# max31855_sensorion_board.net
KiCad netlist of a schematic drawn in Altium Designer
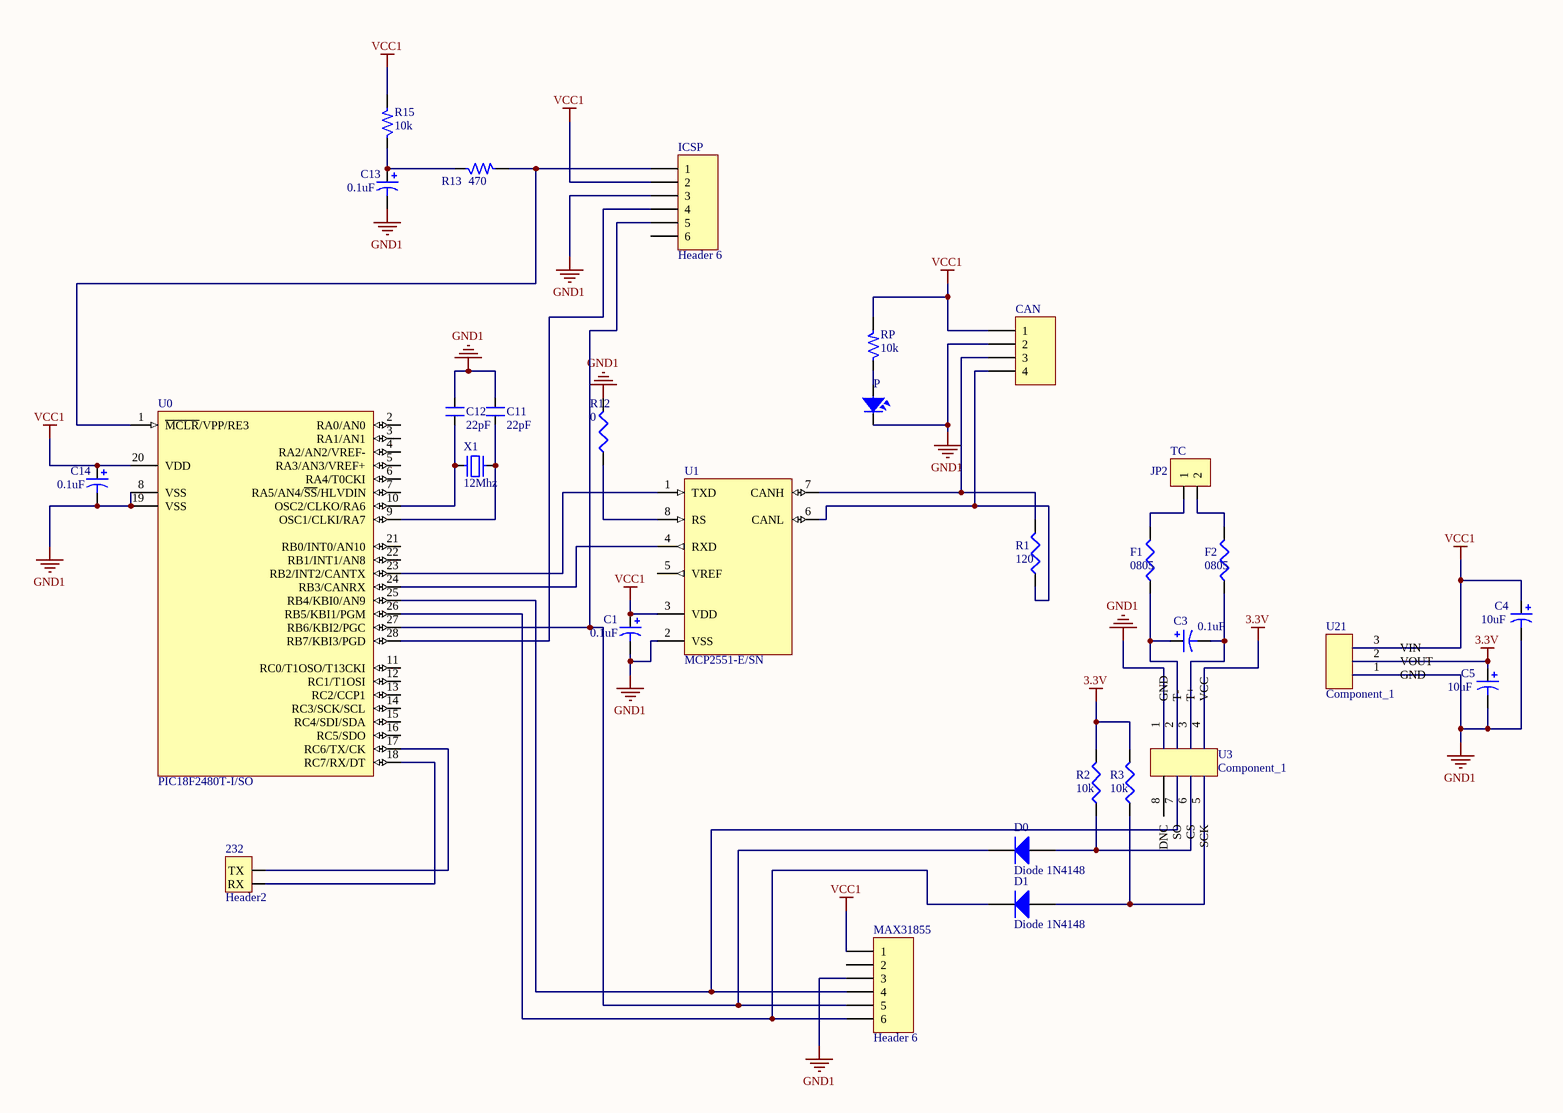
[diagram p0: max31855_sensorion_board.SchDoc]

(export (version "E")
  (design (tool "Eeschema 10.0.6"))
  (components
    (comp (ref "232")
      (value "Header2")
      (footprint "HDR2")
      (description "Header IDC, 2 x 1 Pin Vertical 2.54mm Pitch (Non-Boxed, Male)")
      (fields
        (field (name "MANUFACTURER") "Würth Elektronik eiSos GmbH")
        (field (name "PARTNO") "613002143121")
        (field (name "CREATED BY") "Karrer Zheng")
      )
      (libsource (lib "LIBRARY") (part "Header2"))
    )
    (comp (ref "C1")
      (value "0.1uF")
      (footprint "C0805")
      (description "Polarized Capacitor (Surface Mount)")
      (fields (field (name "Comment") "Cap Pol3") (field (name "PUBLISHER") "Altium Limited"))
      (libsource (lib "Miscellaneous Devices") (part "Cap Pol3"))
    )
    (comp (ref "C3")
      (value "0.1uF")
      (footprint "C0805")
      (description "Polarized Capacitor (Surface Mount)")
      (fields (field (name "Comment") "Cap Pol3") (field (name "PUBLISHER") "Altium Limited"))
      (libsource (lib "Miscellaneous Devices") (part "Cap Pol3"))
    )
    (comp (ref "C4")
      (value "10uF")
      (footprint "C0805")
      (description "Polarized Capacitor (Surface Mount)")
      (fields (field (name "Comment") "Cap Pol3") (field (name "PUBLISHER") "Altium Limited"))
      (libsource (lib "Miscellaneous Devices") (part "Cap Pol3"))
    )
    (comp (ref "C5")
      (value "10uF")
      (footprint "C0805")
      (description "Polarized Capacitor (Surface Mount)")
      (fields (field (name "Comment") "Cap Pol3") (field (name "PUBLISHER") "Altium Limited"))
      (libsource (lib "Miscellaneous Devices") (part "Cap Pol3"))
    )
    (comp (ref "C11")
      (value "22pF")
      (footprint "CN1")
      (description "Cremic For Xtal 1pF => 100pF")
      (libsource (lib "electronicvn-library1") (part "CN0"))
    )
    (comp (ref "C12")
      (value "22pF")
      (footprint "CN1")
      (description "Cremic For Xtal 1pF => 100pF")
      (libsource (lib "electronicvn-library1") (part "CN0"))
    )
    (comp (ref "C13")
      (value "0.1uF")
      (footprint "C0805")
      (description "Polarized Capacitor (Surface Mount)")
      (fields (field (name "Comment") "Cap Pol3") (field (name "PUBLISHER") "Altium Limited"))
      (libsource (lib "Miscellaneous Devices") (part "Cap Pol3"))
    )
    (comp (ref "C14")
      (value "0.1uF")
      (footprint "C0805")
      (description "Polarized Capacitor (Surface Mount)")
      (fields (field (name "Comment") "Cap Pol3") (field (name "PUBLISHER") "Altium Limited"))
      (libsource (lib "Miscellaneous Devices") (part "Cap Pol3"))
    )
    (comp (ref "CAN")
      (value "Header 4")
      (footprint "HDR1X4")
      (description "Header, 4-Pin")
      (fields (field (name "PUBLISHER") "Altium Limited"))
      (libsource (lib "Miscellaneous Connectors") (part "Header 4"))
    )
    (comp (ref "D0")
      (value "Diode 1N4148")
      (footprint "DO-35")
      (description "High Conductance Fast Diode")
      (fields (field (name "PUBLISHER") "Altium Limited"))
      (libsource (lib "Miscellaneous Devices") (part "Diode 1N4148"))
    )
    (comp (ref "D1")
      (value "Diode 1N4148")
      (footprint "DO-35")
      (description "High Conductance Fast Diode")
      (fields (field (name "PUBLISHER") "Altium Limited"))
      (libsource (lib "Miscellaneous Devices") (part "Diode 1N4148"))
    )
    (comp (ref "F1")
      (value "0805")
      (footprint "J1-0603")
      (description "Resistor")
      (fields (field (name "Comment") "Res3") (field (name "PUBLISHER") "Altium Limited"))
      (libsource (lib "Miscellaneous Devices") (part "Res3"))
    )
    (comp (ref "F2")
      (value "0805")
      (footprint "J1-0603")
      (description "Resistor")
      (fields (field (name "Comment") "Res3") (field (name "PUBLISHER") "Altium Limited"))
      (libsource (lib "Miscellaneous Devices") (part "Res3"))
    )
    (comp (ref "ICSP")
      (value "Header 6")
      (footprint "HDR1X6")
      (description "Header, 6-Pin")
      (fields (field (name "PUBLISHER") "Altium Limited"))
      (libsource (lib "Miscellaneous Connectors") (part "Header 6"))
    )
    (comp (ref "MAX31855")
      (value "Header 6")
      (footprint "HDR1X6")
      (description "Header, 6-Pin")
      (fields (field (name "PUBLISHER") "Altium Limited"))
      (libsource (lib "Miscellaneous Connectors") (part "Header 6"))
    )
    (comp (ref "P")
      (value "LED")
      (footprint "LED-3MM-YELLOW")
      (description "LED Single colour Green and Red")
      (libsource (lib "LIBRARY") (part "LED"))
    )
    (comp (ref "R1")
      (value "120")
      (footprint "J1-0603")
      (description "Resistor")
      (fields (field (name "Comment") "Res3") (field (name "PUBLISHER") "Altium Limited"))
      (libsource (lib "Miscellaneous Devices") (part "Res3"))
    )
    (comp (ref "R2")
      (value "10k")
      (footprint "J1-0603")
      (description "Resistor")
      (fields (field (name "Comment") "Res3") (field (name "PUBLISHER") "Altium Limited"))
      (libsource (lib "Miscellaneous Devices") (part "Res3"))
    )
    (comp (ref "R3")
      (value "10k")
      (footprint "J1-0603")
      (description "Resistor")
      (fields (field (name "Comment") "Res3") (field (name "PUBLISHER") "Altium Limited"))
      (libsource (lib "Miscellaneous Devices") (part "Res3"))
    )
    (comp (ref "R12")
      (value "0")
      (footprint "J1-0603")
      (description "Resistor")
      (fields (field (name "Comment") "Res3") (field (name "PUBLISHER") "Altium Limited"))
      (libsource (lib "Miscellaneous Devices") (part "Res3"))
    )
    (comp (ref "R13")
      (value "470")
      (footprint "SM-RES-1206")
      (description "Resistor 1/4W")
      (libsource (lib "electronicvn-library1") (part "R"))
    )
    (comp (ref "R15")
      (value "10k")
      (footprint "SM-RES-1206")
      (description "Resistor 1/4W")
      (libsource (lib "electronicvn-library1") (part "R"))
    )
    (comp (ref "RP")
      (value "10k")
      (footprint "SM-RES-1206")
      (description "Resistor 1/4W")
      (libsource (lib "electronicvn-library1") (part "R"))
    )
    (comp (ref "TC")
      (value "JP2")
      (footprint "JP2-D1T")
      (description "WR-PHD 2.54 mm Angled Socket Header")
      (fields
        (field (name "MANUFACTURER") "Würth Elektronik eiSos GmbH")
        (field (name "PARTNO") "613002143121")
        (field (name "CREATED BY") "Karrer Zheng")
      )
      (libsource (lib "LIBRARY") (part "JP2"))
    )
    (comp (ref "U0")
      (value "PIC18F2480T-I/SO")
      (footprint "SOIC-SO28_L")
      (fields (field (name "PUBLISHER") "Altium Limited"))
      (libsource (lib "Microchip Microcontroller 8-Bit PIC18") (part "PIC18F2480T-I/SO"))
    )
    (comp (ref "U1")
      (value "MCP2551-E/SN")
      (footprint "SOIC-SN8_N")
      (description "High-Speed CAN Transceiver, 8-Pin SOIC, Extended Temperature")
      (fields (field (name "PUBLISHER") "Altium Limited"))
      (libsource (lib "Microchip Interface") (part "MCP2551-E/SN"))
    )
    (comp (ref "U3")
      (value "Component_1")
      (footprint "SOP8 - duplicate")
      (libsource (lib "max31855") (part "Component_1"))
    )
    (comp (ref "U21")
      (value "Component_1")
      (footprint "SOT229P700X460-4N")
      (libsource (lib "AMS1117") (part "Component_1"))
    )
    (comp (ref "X1")
      (value "12Mhz")
      (footprint "XT2")
      (description "Crystal, 32.768 KHz, -40 to 85 degC, 3.2 x 1.5 x 0.9 mm SMD")
      (libsource (lib "LIBRARY") (part "XT2"))
    )
  )
  (nets
    (net (code "1") (name "3.3V") (class "Default")
      (node (ref "C5") (pin "1") (pinfunction "1_1") (pintype "passive"))
      (node (ref "R2") (pin "2") (pinfunction "2_2") (pintype "passive"))
      (node (ref "R3") (pin "2") (pinfunction "2_2") (pintype "passive"))
      (node (ref "U21") (pin "2") (pinfunction "VOUT_2") (pintype "passive"))
      (node (ref "U3") (pin "4") (pinfunction "VCC_4") (pintype "passive"))
    )
    (net (code "2") (name "GND1") (class "Default")
      (node (ref "C1") (pin "2") (pinfunction "2_2") (pintype "passive"))
      (node (ref "C11") (pin "2") (pinfunction "2_2") (pintype "passive"))
      (node (ref "C12") (pin "2") (pinfunction "2_2") (pintype "passive"))
      (node (ref "C13") (pin "2") (pinfunction "2_2") (pintype "passive"))
      (node (ref "C14") (pin "2") (pinfunction "2_2") (pintype "passive"))
      (node (ref "C4") (pin "2") (pinfunction "2_2") (pintype "passive"))
      (node (ref "C5") (pin "2") (pinfunction "2_2") (pintype "passive"))
      (node (ref "CAN") (pin "2") (pinfunction "2_2") (pintype "passive"))
      (node (ref "ICSP") (pin "3") (pinfunction "3_3") (pintype "passive"))
      (node (ref "MAX31855") (pin "3") (pinfunction "3_3") (pintype "passive"))
      (node (ref "P") (pin "2") (pinfunction "2_2") (pintype "passive"))
      (node (ref "R12") (pin "2") (pinfunction "2_2") (pintype "passive"))
      (node (ref "U0") (pin "19") (pinfunction "VSS_19") (pintype "power_in"))
      (node (ref "U0") (pin "8") (pinfunction "VSS_8") (pintype "power_in"))
      (node (ref "U1") (pin "2") (pinfunction "VSS_2") (pintype "power_in"))
      (node (ref "U21") (pin "1") (pinfunction "GND_1") (pintype "passive"))
      (node (ref "U3") (pin "1") (pinfunction "GND_1") (pintype "passive"))
    )
    (net (code "3") (name "Net-(232-RX)") (class "Default")
      (node (ref "232") (pin "1") (pinfunction "RX_1") (pintype "passive"))
      (node (ref "U0") (pin "18") (pinfunction "RC7/RX/DT_18") (pintype "bidirectional"))
    )
    (net (code "4") (name "Net-(232-TX)") (class "Default")
      (node (ref "232") (pin "2") (pinfunction "TX_2") (pintype "passive"))
      (node (ref "U0") (pin "17") (pinfunction "RC6/TX/CK_17") (pintype "bidirectional"))
    )
    (net (code "5") (name "Net-(C13-Pad1)") (class "Default")
      (node (ref "C13") (pin "1") (pinfunction "1_1") (pintype "passive"))
      (node (ref "R13") (pin "1") (pinfunction "1_1") (pintype "passive"))
      (node (ref "R15") (pin "1") (pinfunction "1_1") (pintype "passive"))
    )
    (net (code "6") (name "Net-(D0-A)") (class "Default")
      (node (ref "D0") (pin "1") (pinfunction "A_1") (pintype "passive"))
      (node (ref "R2") (pin "1") (pinfunction "1_1") (pintype "passive"))
      (node (ref "U3") (pin "6") (pinfunction "CS_6") (pintype "passive"))
    )
    (net (code "7") (name "Net-(D0-K)") (class "Default")
      (node (ref "D0") (pin "2") (pinfunction "K_2") (pintype "passive"))
      (node (ref "ICSP") (pin "5") (pinfunction "5_5") (pintype "passive"))
      (node (ref "MAX31855") (pin "5") (pinfunction "5_5") (pintype "passive"))
      (node (ref "U0") (pin "27") (pinfunction "RB6/KBI2/PGC_27") (pintype "bidirectional"))
    )
    (net (code "8") (name "Net-(D1-A)") (class "Default")
      (node (ref "D1") (pin "1") (pinfunction "A_1") (pintype "passive"))
      (node (ref "R3") (pin "1") (pinfunction "1_1") (pintype "passive"))
      (node (ref "U3") (pin "5") (pinfunction "SCK_5") (pintype "passive"))
    )
    (net (code "9") (name "Net-(D1-K)") (class "Default")
      (node (ref "D1") (pin "2") (pinfunction "K_2") (pintype "passive"))
      (node (ref "MAX31855") (pin "6") (pinfunction "6_6") (pintype "passive"))
      (node (ref "U0") (pin "26") (pinfunction "RB5/KBI1/PGM_26") (pintype "bidirectional"))
    )
    (net (code "10") (name "Net-(F1-Pad2)") (class "Default")
      (node (ref "F1") (pin "2") (pinfunction "2_2") (pintype "passive"))
      (node (ref "TC") (pin "1") (pinfunction "1_1") (pintype "passive"))
    )
    (net (code "11") (name "Net-(F2-Pad2)") (class "Default")
      (node (ref "F2") (pin "2") (pinfunction "2_2") (pintype "passive"))
      (node (ref "TC") (pin "2") (pinfunction "2_2") (pintype "passive"))
    )
    (net (code "12") (name "Net-(P-Pad1)") (class "Default")
      (node (ref "P") (pin "1") (pinfunction "1_1") (pintype "passive"))
      (node (ref "RP") (pin "1") (pinfunction "1_1") (pintype "passive"))
    )
    (net (code "13") (name "Net-(U0-OSC1{slash}CLKI{slash}RA7)") (class "Default")
      (node (ref "C11") (pin "1") (pinfunction "1_1") (pintype "passive"))
      (node (ref "U0") (pin "9") (pinfunction "OSC1/CLKI/RA7_9") (pintype "bidirectional"))
      (node (ref "X1") (pin "2") (pinfunction "2_2") (pintype "passive"))
    )
    (net (code "14") (name "Net-(U0-OSC2{slash}CLKO{slash}RA6)") (class "Default")
      (node (ref "C12") (pin "1") (pinfunction "1_1") (pintype "passive"))
      (node (ref "U0") (pin "10") (pinfunction "OSC2/CLKO/RA6_10") (pintype "bidirectional"))
      (node (ref "X1") (pin "1") (pinfunction "1_1") (pintype "passive"))
    )
    (net (code "15") (name "Net-(U0-RB2{slash}INT2{slash}CANTX)") (class "Default")
      (node (ref "U0") (pin "23") (pinfunction "RB2/INT2/CANTX_23") (pintype "bidirectional"))
      (node (ref "U1") (pin "1") (pinfunction "TXD_1") (pintype "input"))
    )
    (net (code "16") (name "Net-(U0-RB3{slash}CANRX)") (class "Default")
      (node (ref "U0") (pin "24") (pinfunction "RB3/CANRX_24") (pintype "bidirectional"))
      (node (ref "U1") (pin "4") (pinfunction "RXD_4") (pintype "output"))
    )
    (net (code "17") (name "Net-(U0-RB4{slash}KBI0{slash}AN9)") (class "Default")
      (node (ref "MAX31855") (pin "4") (pinfunction "4_4") (pintype "passive"))
      (node (ref "U0") (pin "25") (pinfunction "RB4/KBI0/AN9_25") (pintype "bidirectional"))
      (node (ref "U3") (pin "7") (pinfunction "SO_7") (pintype "passive"))
    )
    (net (code "18") (name "Net-(U0-RB7{slash}KBI3{slash}PGD)") (class "Default")
      (node (ref "ICSP") (pin "4") (pinfunction "4_4") (pintype "passive"))
      (node (ref "U0") (pin "28") (pinfunction "RB7/KBI3/PGD_28") (pintype "bidirectional"))
    )
    (net (code "19") (name "Net-(U0-~{MCLR}{slash}VPP{slash}RE3)") (class "Default")
      (node (ref "ICSP") (pin "1") (pinfunction "1_1") (pintype "passive"))
      (node (ref "R13") (pin "2") (pinfunction "2_2") (pintype "passive"))
      (node (ref "U0") (pin "1") (pinfunction "~{MCLR}/VPP/RE3_1") (pintype "input"))
    )
    (net (code "20") (name "Net-(U1-CANH)") (class "Default")
      (node (ref "CAN") (pin "3") (pinfunction "3_3") (pintype "passive"))
      (node (ref "R1") (pin "2") (pinfunction "2_2") (pintype "passive"))
      (node (ref "U1") (pin "7") (pinfunction "CANH_7") (pintype "bidirectional"))
    )
    (net (code "21") (name "Net-(U1-CANL)") (class "Default")
      (node (ref "CAN") (pin "4") (pinfunction "4_4") (pintype "passive"))
      (node (ref "R1") (pin "1") (pinfunction "1_1") (pintype "passive"))
      (node (ref "U1") (pin "6") (pinfunction "CANL_6") (pintype "bidirectional"))
    )
    (net (code "22") (name "Net-(U1-RS)") (class "Default")
      (node (ref "R12") (pin "1") (pinfunction "1_1") (pintype "passive"))
      (node (ref "U1") (pin "8") (pinfunction "RS_8") (pintype "input"))
    )
    (net (code "23") (name "Net-(U3-T+)") (class "Default")
      (node (ref "C3") (pin "2") (pinfunction "2_2") (pintype "passive"))
      (node (ref "F2") (pin "1") (pinfunction "1_1") (pintype "passive"))
      (node (ref "U3") (pin "3") (pinfunction "T+_3") (pintype "passive"))
    )
    (net (code "24") (name "Net-(U3-T-)") (class "Default")
      (node (ref "C3") (pin "1") (pinfunction "1_1") (pintype "passive"))
      (node (ref "F1") (pin "1") (pinfunction "1_1") (pintype "passive"))
      (node (ref "U3") (pin "2") (pinfunction "T-_2") (pintype "passive"))
    )
    (net (code "25") (name "VCC1") (class "Default")
      (node (ref "C1") (pin "1") (pinfunction "1_1") (pintype "passive"))
      (node (ref "C14") (pin "1") (pinfunction "1_1") (pintype "passive"))
      (node (ref "C4") (pin "1") (pinfunction "1_1") (pintype "passive"))
      (node (ref "CAN") (pin "1") (pinfunction "1_1") (pintype "passive"))
      (node (ref "ICSP") (pin "2") (pinfunction "2_2") (pintype "passive"))
      (node (ref "MAX31855") (pin "1") (pinfunction "1_1") (pintype "passive"))
      (node (ref "R15") (pin "2") (pinfunction "2_2") (pintype "passive"))
      (node (ref "RP") (pin "2") (pinfunction "2_2") (pintype "passive"))
      (node (ref "U0") (pin "20") (pinfunction "VDD_20") (pintype "power_in"))
      (node (ref "U1") (pin "3") (pinfunction "VDD_3") (pintype "power_in"))
      (node (ref "U21") (pin "3") (pinfunction "VIN_3") (pintype "passive"))
    )
    (net (code "26") (name "unconnected-(ICSP-Pad6)") (class "Default")
      (node (ref "ICSP") (pin "6") (pinfunction "6_6") (pintype "passive"))
    )
    (net (code "27") (name "unconnected-(MAX31855-Pad2)") (class "Default")
      (node (ref "MAX31855") (pin "2") (pinfunction "2_2") (pintype "passive"))
    )
    (net (code "28") (name "unconnected-(U0-RA0{slash}AN0-Pad2)") (class "Default")
      (node (ref "U0") (pin "2") (pinfunction "RA0/AN0_2") (pintype "bidirectional"))
    )
    (net (code "29") (name "unconnected-(U0-RA1{slash}AN1-Pad3)") (class "Default")
      (node (ref "U0") (pin "3") (pinfunction "RA1/AN1_3") (pintype "bidirectional"))
    )
    (net (code "30") (name "unconnected-(U0-RA2{slash}AN2{slash}VREF--Pad4)") (class "Default")
      (node (ref "U0") (pin "4") (pinfunction "RA2/AN2/VREF-_4") (pintype "bidirectional"))
    )
    (net (code "31") (name "unconnected-(U0-RA3{slash}AN3{slash}VREF+-Pad5)") (class "Default")
      (node (ref "U0") (pin "5") (pinfunction "RA3/AN3/VREF+_5") (pintype "bidirectional"))
    )
    (net (code "32") (name "unconnected-(U0-RA4{slash}T0CKI-Pad6)") (class "Default")
      (node (ref "U0") (pin "6") (pinfunction "RA4/T0CKI_6") (pintype "bidirectional"))
    )
    (net (code "33") (name "unconnected-(U0-RA5{slash}AN4{slash}~{SS}{slash}HLVDIN-Pad7)") (class "Default")
      (node (ref "U0") (pin "7") (pinfunction "RA5/AN4/~{SS}/HLVDIN_7") (pintype "bidirectional"))
    )
    (net (code "34") (name "unconnected-(U0-RB0{slash}INT0{slash}AN10-Pad21)") (class "Default")
      (node (ref "U0") (pin "21") (pinfunction "RB0/INT0/AN10_21") (pintype "bidirectional"))
    )
    (net (code "35") (name "unconnected-(U0-RB1{slash}INT1{slash}AN8-Pad22)") (class "Default")
      (node (ref "U0") (pin "22") (pinfunction "RB1/INT1/AN8_22") (pintype "bidirectional"))
    )
    (net (code "36") (name "unconnected-(U0-RC0{slash}T1OSO{slash}T13CKI-Pad11)") (class "Default")
      (node (ref "U0") (pin "11") (pinfunction "RC0/T1OSO/T13CKI_11") (pintype "bidirectional"))
    )
    (net (code "37") (name "unconnected-(U0-RC1{slash}T1OSI-Pad12)") (class "Default")
      (node (ref "U0") (pin "12") (pinfunction "RC1/T1OSI_12") (pintype "bidirectional"))
    )
    (net (code "38") (name "unconnected-(U0-RC2{slash}CCP1-Pad13)") (class "Default")
      (node (ref "U0") (pin "13") (pinfunction "RC2/CCP1_13") (pintype "bidirectional"))
    )
    (net (code "39") (name "unconnected-(U0-RC3{slash}SCK{slash}SCL-Pad14)") (class "Default")
      (node (ref "U0") (pin "14") (pinfunction "RC3/SCK/SCL_14") (pintype "bidirectional"))
    )
    (net (code "40") (name "unconnected-(U0-RC4{slash}SDI{slash}SDA-Pad15)") (class "Default")
      (node (ref "U0") (pin "15") (pinfunction "RC4/SDI/SDA_15") (pintype "bidirectional"))
    )
    (net (code "41") (name "unconnected-(U0-RC5{slash}SDO-Pad16)") (class "Default")
      (node (ref "U0") (pin "16") (pinfunction "RC5/SDO_16") (pintype "bidirectional"))
    )
    (net (code "42") (name "unconnected-(U1-VREF-Pad5)") (class "Default")
      (node (ref "U1") (pin "5") (pinfunction "VREF_5") (pintype "output"))
    )
    (net (code "43") (name "unconnected-(U3-DNC-Pad8)") (class "Default")
      (node (ref "U3") (pin "8") (pinfunction "DNC_8") (pintype "passive"))
    )
  )
)
